# Sheet1.net
KiCad netlist of a schematic drawn in Altium Designer
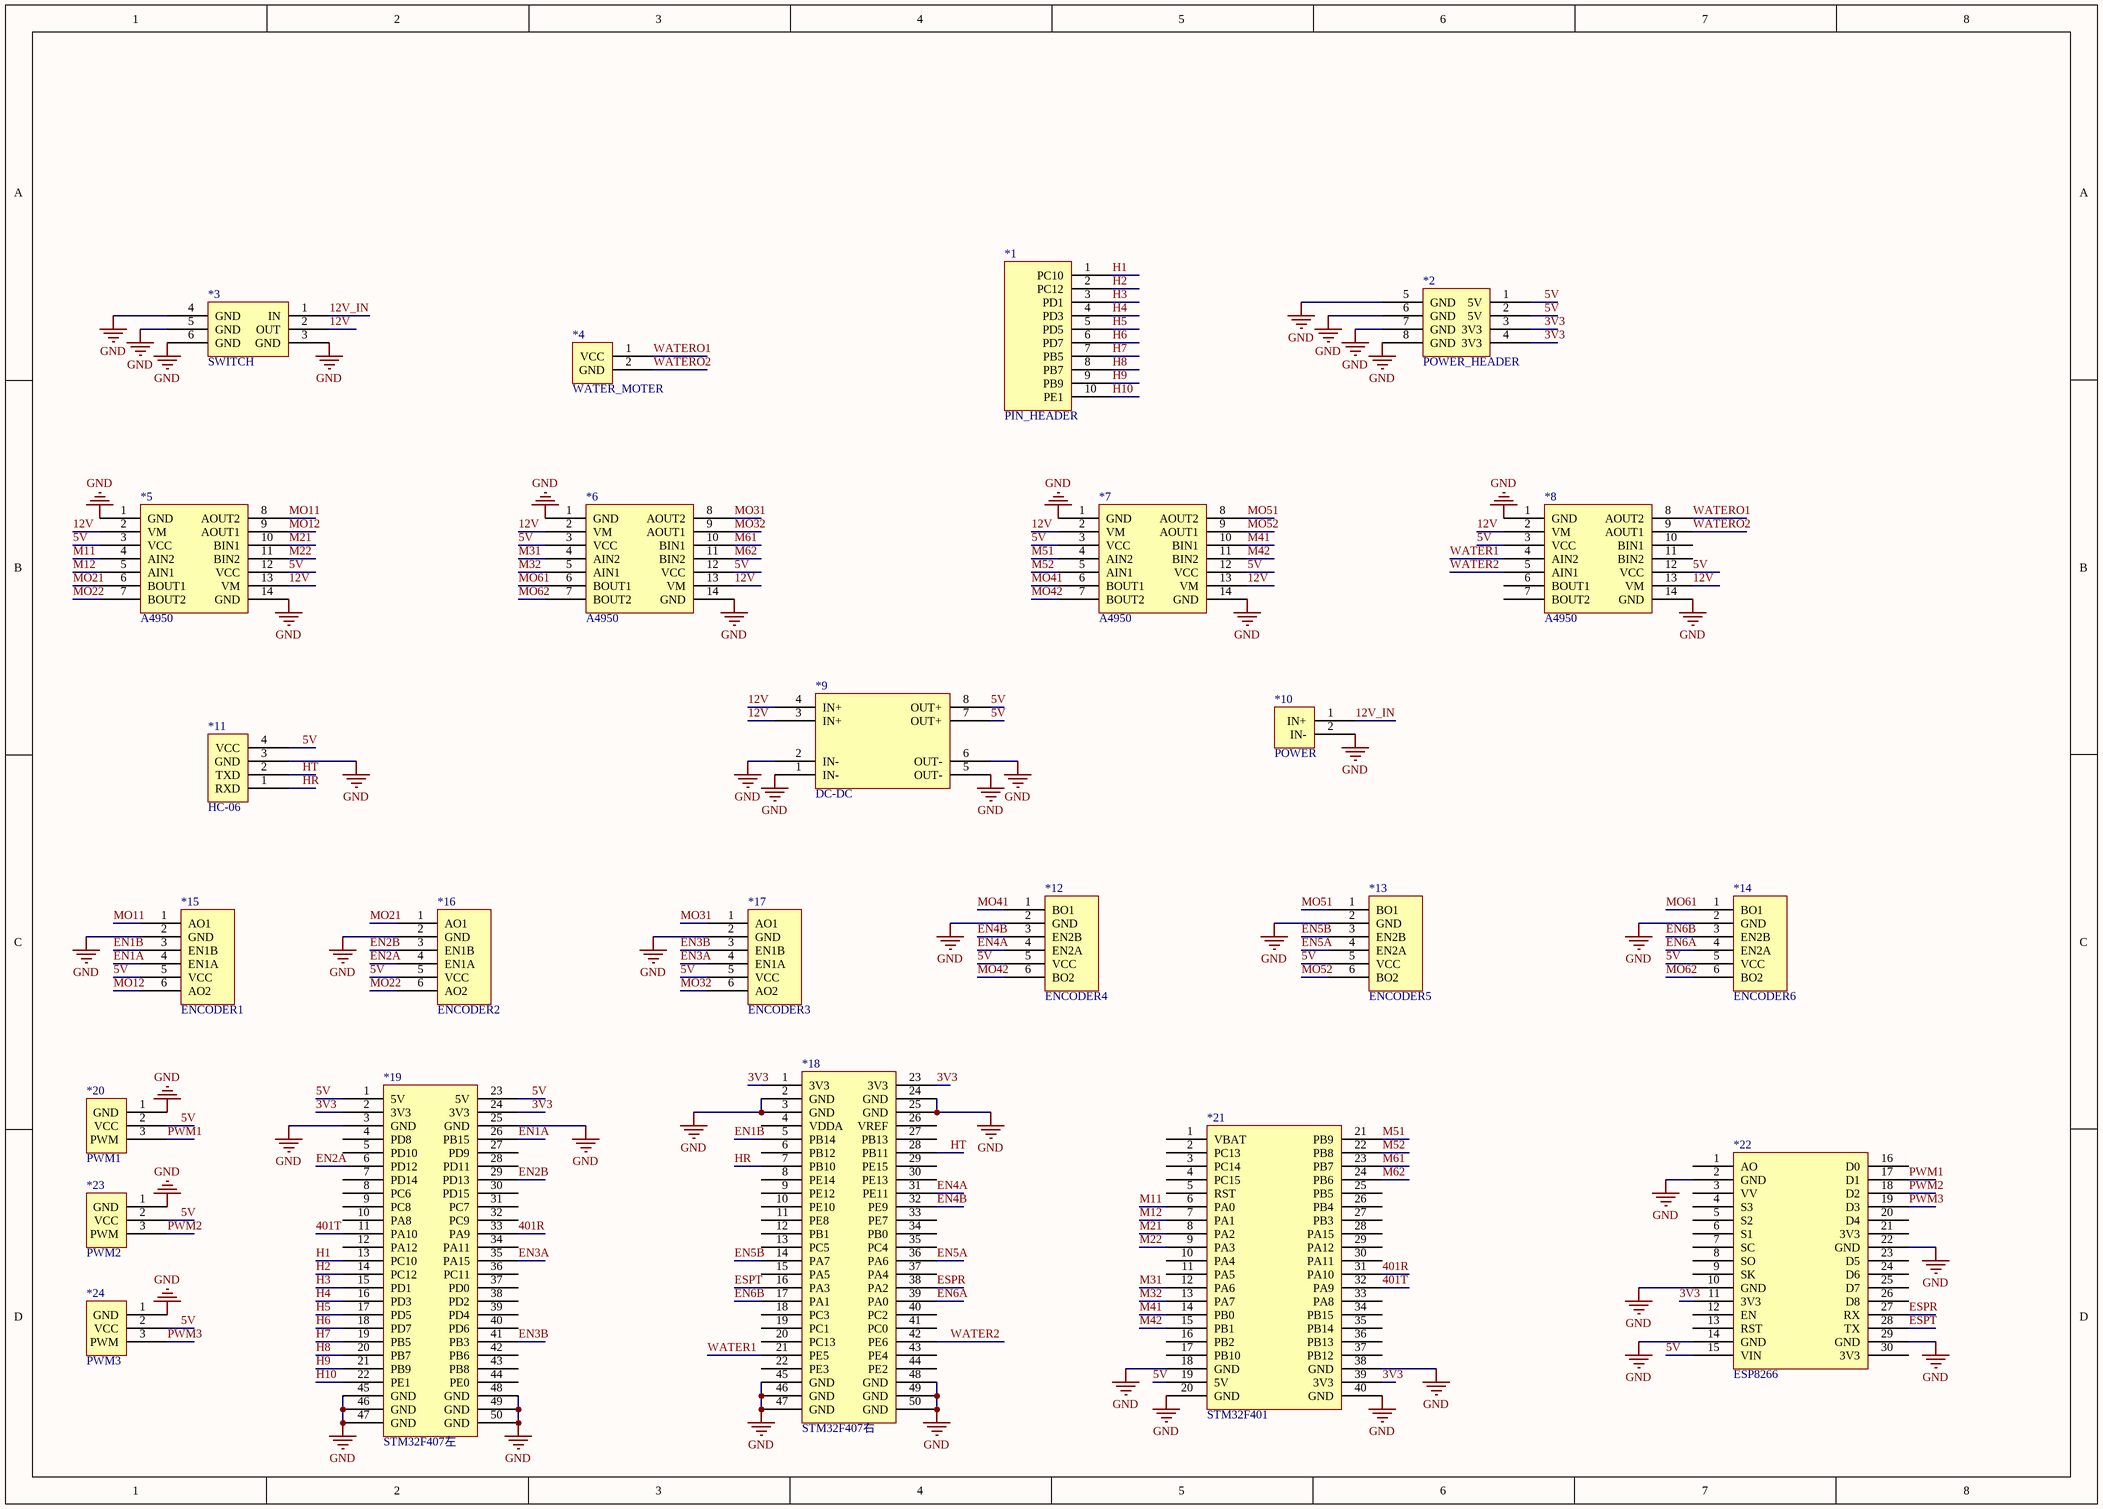
[diagram p0: Sheet1.SchDoc]

(export (version "E")
  (design (tool "Eeschema 10.0.6"))
  (components
    (comp (ref "*1")
      (value "PIN_HEADER")
      (footprint "PIN_HEADER")
      (libsource (lib "Schlib1") (part "PIN_HEADER"))
    )
    (comp (ref "*2")
      (value "POWER_HEADER")
      (footprint "POWER_HEADER")
      (libsource (lib "Schlib1") (part "POWER_HEADER"))
    )
    (comp (ref "*3") (value "SWITCH") (footprint "SIWITCH") (libsource (lib "Schlib1") (part "SWITCH")))
    (comp (ref "*4")
      (value "WATER_MOTER")
      (footprint "WATER_HEADER")
      (libsource (lib "Schlib1") (part "WATER_MOTER"))
    )
    (comp (ref "*5") (value "A4950") (footprint "A4950") (libsource (lib "Schlib1") (part "A4950")))
    (comp (ref "*6") (value "A4950") (footprint "A4950") (libsource (lib "Schlib1") (part "A4950")))
    (comp (ref "*7") (value "A4950") (footprint "A4950") (libsource (lib "Schlib1") (part "A4950")))
    (comp (ref "*8") (value "A4950") (footprint "A4950") (libsource (lib "Schlib1") (part "A4950")))
    (comp (ref "*9") (value "DC-DC") (footprint "DC-DC") (libsource (lib "Schlib1") (part "DC-DC")))
    (comp (ref "*10") (value "POWER") (footprint "POWER") (libsource (lib "Schlib1") (part "POWER")))
    (comp (ref "*11") (value "HC-06") (footprint "HC-06") (libsource (lib "Schlib1") (part "HC-06")))
    (comp (ref "*12") (value "ENCODER4") (footprint "ENCODER2") (libsource (lib "Schlib1") (part "ENCODER4")))
    (comp (ref "*13") (value "ENCODER5") (footprint "ENCODER2") (libsource (lib "Schlib1") (part "ENCODER5")))
    (comp (ref "*14") (value "ENCODER6") (footprint "ENCODER2") (libsource (lib "Schlib1") (part "ENCODER6")))
    (comp (ref "*15") (value "ENCODER1") (footprint "ENCODER1") (libsource (lib "Schlib1") (part "ENCODER1")))
    (comp (ref "*16") (value "ENCODER2") (footprint "ENCODER1") (libsource (lib "Schlib1") (part "ENCODER2")))
    (comp (ref "*17") (value "ENCODER3") (footprint "ENCODER1") (libsource (lib "Schlib1") (part "ENCODER3")))
    (comp (ref "*18")
      (value "STM32F407右")
      (footprint "STM32F407左")
      (libsource (lib "Schlib1") (part "STM32F407右"))
    )
    (comp (ref "*19")
      (value "STM32F407左")
      (footprint "STM32F407左")
      (libsource (lib "Schlib1") (part "STM32F407左"))
    )
    (comp (ref "*20") (value "PWM1") (footprint "PWM") (libsource (lib "Schlib1") (part "PWM1")))
    (comp (ref "*21")
      (value "STM32F401")
      (footprint "STM32F401CCU6")
      (libsource (lib "Schlib1") (part "STM32F401"))
    )
    (comp (ref "*22") (value "ESP8266") (footprint "ESP") (libsource (lib "Schlib1") (part "ESP8266")))
    (comp (ref "*23") (value "PWM2") (footprint "PWM") (libsource (lib "Schlib1") (part "PWM2")))
    (comp (ref "*24") (value "PWM3") (footprint "PWM") (libsource (lib "Schlib1") (part "PWM3")))
  )
  (nets
    (net (code "1") (name "/3V3") (class "Default")
      (node (ref "*18") (pin "1") (pinfunction "3V3_1") (pintype "passive"))
      (node (ref "*18") (pin "23") (pinfunction "3V3_23") (pintype "passive"))
      (node (ref "*19") (pin "2") (pinfunction "3V3_2") (pintype "passive"))
      (node (ref "*19") (pin "24") (pinfunction "3V3_24") (pintype "passive"))
      (node (ref "*2") (pin "3") (pinfunction "3V3_3") (pintype "passive"))
      (node (ref "*2") (pin "4") (pinfunction "3V3_4") (pintype "passive"))
      (node (ref "*21") (pin "39") (pinfunction "3V3_39") (pintype "passive"))
      (node (ref "*22") (pin "11") (pinfunction "3V3_11") (pintype "passive"))
    )
    (net (code "2") (name "/5V") (class "Default")
      (node (ref "*11") (pin "4") (pinfunction "VCC_4") (pintype "passive"))
      (node (ref "*12") (pin "5") (pinfunction "VCC_5") (pintype "passive"))
      (node (ref "*13") (pin "5") (pinfunction "VCC_5") (pintype "passive"))
      (node (ref "*14") (pin "5") (pinfunction "VCC_5") (pintype "passive"))
      (node (ref "*15") (pin "5") (pinfunction "VCC_5") (pintype "passive"))
      (node (ref "*16") (pin "5") (pinfunction "VCC_5") (pintype "passive"))
      (node (ref "*17") (pin "5") (pinfunction "VCC_5") (pintype "passive"))
      (node (ref "*19") (pin "1") (pinfunction "5V_1") (pintype "passive"))
      (node (ref "*19") (pin "23") (pinfunction "5V_23") (pintype "passive"))
      (node (ref "*2") (pin "1") (pinfunction "5V_1") (pintype "passive"))
      (node (ref "*2") (pin "2") (pinfunction "5V_2") (pintype "passive"))
      (node (ref "*20") (pin "2") (pinfunction "VCC_2") (pintype "passive"))
      (node (ref "*21") (pin "19") (pinfunction "5V_19") (pintype "passive"))
      (node (ref "*22") (pin "15") (pinfunction "VIN_15") (pintype "passive"))
      (node (ref "*23") (pin "2") (pinfunction "VCC_2") (pintype "passive"))
      (node (ref "*24") (pin "2") (pinfunction "VCC_2") (pintype "passive"))
      (node (ref "*5") (pin "12") (pinfunction "VCC_12") (pintype "passive"))
      (node (ref "*5") (pin "3") (pinfunction "VCC_3") (pintype "passive"))
      (node (ref "*6") (pin "12") (pinfunction "VCC_12") (pintype "passive"))
      (node (ref "*6") (pin "3") (pinfunction "VCC_3") (pintype "passive"))
      (node (ref "*7") (pin "12") (pinfunction "VCC_12") (pintype "passive"))
      (node (ref "*7") (pin "3") (pinfunction "VCC_3") (pintype "passive"))
      (node (ref "*8") (pin "12") (pinfunction "VCC_12") (pintype "passive"))
      (node (ref "*8") (pin "3") (pinfunction "VCC_3") (pintype "passive"))
      (node (ref "*9") (pin "7") (pinfunction "OUT+_7") (pintype "passive"))
      (node (ref "*9") (pin "8") (pinfunction "OUT+_8") (pintype "passive"))
    )
    (net (code "3") (name "/12V") (class "Default")
      (node (ref "*3") (pin "2") (pinfunction "OUT_2") (pintype "passive"))
      (node (ref "*5") (pin "13") (pinfunction "VM_13") (pintype "passive"))
      (node (ref "*5") (pin "2") (pinfunction "VM_2") (pintype "passive"))
      (node (ref "*6") (pin "13") (pinfunction "VM_13") (pintype "passive"))
      (node (ref "*6") (pin "2") (pinfunction "VM_2") (pintype "passive"))
      (node (ref "*7") (pin "13") (pinfunction "VM_13") (pintype "passive"))
      (node (ref "*7") (pin "2") (pinfunction "VM_2") (pintype "passive"))
      (node (ref "*8") (pin "13") (pinfunction "VM_13") (pintype "passive"))
      (node (ref "*8") (pin "2") (pinfunction "VM_2") (pintype "passive"))
      (node (ref "*9") (pin "3") (pinfunction "IN+_3") (pintype "passive"))
      (node (ref "*9") (pin "4") (pinfunction "IN+_4") (pintype "passive"))
    )
    (net (code "4") (name "/12V_IN") (class "Default")
      (node (ref "*10") (pin "1") (pinfunction "IN+_1") (pintype "passive"))
      (node (ref "*3") (pin "1") (pinfunction "IN_1") (pintype "passive"))
    )
    (net (code "5") (name "/401R") (class "Default")
      (node (ref "*19") (pin "33") (pinfunction "PA9_33") (pintype "passive"))
      (node (ref "*21") (pin "31") (pinfunction "PA10_31") (pintype "passive"))
    )
    (net (code "6") (name "/401T") (class "Default")
      (node (ref "*19") (pin "11") (pinfunction "PA10_11") (pintype "passive"))
      (node (ref "*21") (pin "32") (pinfunction "PA9_32") (pintype "passive"))
    )
    (net (code "7") (name "/EN1A") (class "Default")
      (node (ref "*15") (pin "4") (pinfunction "EN1A_4") (pintype "passive"))
      (node (ref "*19") (pin "26") (pinfunction "PB15_26") (pintype "passive"))
    )
    (net (code "8") (name "/EN1B") (class "Default")
      (node (ref "*15") (pin "3") (pinfunction "EN1B_3") (pintype "passive"))
      (node (ref "*18") (pin "5") (pinfunction "PB14_5") (pintype "passive"))
    )
    (net (code "9") (name "/EN2A") (class "Default")
      (node (ref "*16") (pin "4") (pinfunction "EN1A_4") (pintype "passive"))
      (node (ref "*19") (pin "6") (pinfunction "PD12_6") (pintype "passive"))
    )
    (net (code "10") (name "/EN2B") (class "Default")
      (node (ref "*16") (pin "3") (pinfunction "EN1B_3") (pintype "passive"))
      (node (ref "*19") (pin "29") (pinfunction "PD13_29") (pintype "passive"))
    )
    (net (code "11") (name "/EN3A") (class "Default")
      (node (ref "*17") (pin "4") (pinfunction "EN1A_4") (pintype "passive"))
      (node (ref "*19") (pin "35") (pinfunction "PA15_35") (pintype "passive"))
    )
    (net (code "12") (name "/EN3B") (class "Default")
      (node (ref "*17") (pin "3") (pinfunction "EN1B_3") (pintype "passive"))
      (node (ref "*19") (pin "41") (pinfunction "PB3_41") (pintype "passive"))
    )
    (net (code "13") (name "/EN4A") (class "Default")
      (node (ref "*12") (pin "4") (pinfunction "EN2A_4") (pintype "passive"))
      (node (ref "*18") (pin "31") (pinfunction "PE11_31") (pintype "passive"))
    )
    (net (code "14") (name "/EN4B") (class "Default")
      (node (ref "*12") (pin "3") (pinfunction "EN2B_3") (pintype "passive"))
      (node (ref "*18") (pin "32") (pinfunction "PE9_32") (pintype "passive"))
    )
    (net (code "15") (name "/EN5A") (class "Default")
      (node (ref "*13") (pin "4") (pinfunction "EN2A_4") (pintype "passive"))
      (node (ref "*18") (pin "36") (pinfunction "PA6_36") (pintype "passive"))
    )
    (net (code "16") (name "/EN5B") (class "Default")
      (node (ref "*13") (pin "3") (pinfunction "EN2B_3") (pintype "passive"))
      (node (ref "*18") (pin "14") (pinfunction "PA7_14") (pintype "passive"))
    )
    (net (code "17") (name "/EN6A") (class "Default")
      (node (ref "*14") (pin "4") (pinfunction "EN2A_4") (pintype "passive"))
      (node (ref "*18") (pin "39") (pinfunction "PA0_39") (pintype "passive"))
    )
    (net (code "18") (name "/EN6B") (class "Default")
      (node (ref "*14") (pin "3") (pinfunction "EN2B_3") (pintype "passive"))
      (node (ref "*18") (pin "17") (pinfunction "PA1_17") (pintype "passive"))
    )
    (net (code "19") (name "/ESPR") (class "Default")
      (node (ref "*18") (pin "38") (pinfunction "PA2_38") (pintype "passive"))
      (node (ref "*22") (pin "27") (pinfunction "RX_27") (pintype "passive"))
    )
    (net (code "20") (name "/ESPT") (class "Default")
      (node (ref "*18") (pin "16") (pinfunction "PA3_16") (pintype "passive"))
      (node (ref "*22") (pin "28") (pinfunction "TX_28") (pintype "passive"))
    )
    (net (code "21") (name "/H1") (class "Default")
      (node (ref "*1") (pin "1") (pinfunction "PC10_1") (pintype "passive"))
      (node (ref "*19") (pin "13") (pinfunction "PC10_13") (pintype "passive"))
    )
    (net (code "22") (name "/H2") (class "Default")
      (node (ref "*1") (pin "2") (pinfunction "PC12_2") (pintype "passive"))
      (node (ref "*19") (pin "14") (pinfunction "PC12_14") (pintype "passive"))
    )
    (net (code "23") (name "/H3") (class "Default")
      (node (ref "*1") (pin "3") (pinfunction "PD1_3") (pintype "passive"))
      (node (ref "*19") (pin "15") (pinfunction "PD1_15") (pintype "passive"))
    )
    (net (code "24") (name "/H4") (class "Default")
      (node (ref "*1") (pin "4") (pinfunction "PD3_4") (pintype "passive"))
      (node (ref "*19") (pin "16") (pinfunction "PD3_16") (pintype "passive"))
    )
    (net (code "25") (name "/H5") (class "Default")
      (node (ref "*1") (pin "5") (pinfunction "PD5_5") (pintype "passive"))
      (node (ref "*19") (pin "17") (pinfunction "PD5_17") (pintype "passive"))
    )
    (net (code "26") (name "/H6") (class "Default")
      (node (ref "*1") (pin "6") (pinfunction "PD7_6") (pintype "passive"))
      (node (ref "*19") (pin "18") (pinfunction "PD7_18") (pintype "passive"))
    )
    (net (code "27") (name "/H7") (class "Default")
      (node (ref "*1") (pin "7") (pinfunction "PB5_7") (pintype "passive"))
      (node (ref "*19") (pin "19") (pinfunction "PB5_19") (pintype "passive"))
    )
    (net (code "28") (name "/H8") (class "Default")
      (node (ref "*1") (pin "8") (pinfunction "PB7_8") (pintype "passive"))
      (node (ref "*19") (pin "20") (pinfunction "PB7_20") (pintype "passive"))
    )
    (net (code "29") (name "/H9") (class "Default")
      (node (ref "*1") (pin "9") (pinfunction "PB9_9") (pintype "passive"))
      (node (ref "*19") (pin "21") (pinfunction "PB9_21") (pintype "passive"))
    )
    (net (code "30") (name "/H10") (class "Default")
      (node (ref "*1") (pin "10") (pinfunction "PE1_10") (pintype "passive"))
      (node (ref "*19") (pin "22") (pinfunction "PE1_22") (pintype "passive"))
    )
    (net (code "31") (name "/HR") (class "Default")
      (node (ref "*11") (pin "1") (pinfunction "RXD_1") (pintype "passive"))
      (node (ref "*18") (pin "7") (pinfunction "PB10_7") (pintype "passive"))
    )
    (net (code "32") (name "/HT") (class "Default")
      (node (ref "*11") (pin "2") (pinfunction "TXD_2") (pintype "passive"))
      (node (ref "*18") (pin "28") (pinfunction "PB11_28") (pintype "passive"))
    )
    (net (code "33") (name "/M11") (class "Default")
      (node (ref "*21") (pin "6") (pinfunction "PA0_6") (pintype "passive"))
      (node (ref "*5") (pin "4") (pinfunction "AIN2_4") (pintype "passive"))
    )
    (net (code "34") (name "/M12") (class "Default")
      (node (ref "*21") (pin "7") (pinfunction "PA1_7") (pintype "passive"))
      (node (ref "*5") (pin "5") (pinfunction "AIN1_5") (pintype "passive"))
    )
    (net (code "35") (name "/M21") (class "Default")
      (node (ref "*21") (pin "8") (pinfunction "PA2_8") (pintype "passive"))
      (node (ref "*5") (pin "10") (pinfunction "BIN1_10") (pintype "passive"))
    )
    (net (code "36") (name "/M22") (class "Default")
      (node (ref "*21") (pin "9") (pinfunction "PA3_9") (pintype "passive"))
      (node (ref "*5") (pin "11") (pinfunction "BIN2_11") (pintype "passive"))
    )
    (net (code "37") (name "/M31") (class "Default")
      (node (ref "*21") (pin "12") (pinfunction "PA6_12") (pintype "passive"))
      (node (ref "*6") (pin "4") (pinfunction "AIN2_4") (pintype "passive"))
    )
    (net (code "38") (name "/M32") (class "Default")
      (node (ref "*21") (pin "13") (pinfunction "PA7_13") (pintype "passive"))
      (node (ref "*6") (pin "5") (pinfunction "AIN1_5") (pintype "passive"))
    )
    (net (code "39") (name "/M41") (class "Default")
      (node (ref "*21") (pin "14") (pinfunction "PB0_14") (pintype "passive"))
      (node (ref "*7") (pin "10") (pinfunction "BIN1_10") (pintype "passive"))
    )
    (net (code "40") (name "/M42") (class "Default")
      (node (ref "*21") (pin "15") (pinfunction "PB1_15") (pintype "passive"))
      (node (ref "*7") (pin "11") (pinfunction "BIN2_11") (pintype "passive"))
    )
    (net (code "41") (name "/M51") (class "Default")
      (node (ref "*21") (pin "21") (pinfunction "PB9_21") (pintype "passive"))
      (node (ref "*7") (pin "4") (pinfunction "AIN2_4") (pintype "passive"))
    )
    (net (code "42") (name "/M52") (class "Default")
      (node (ref "*21") (pin "22") (pinfunction "PB8_22") (pintype "passive"))
      (node (ref "*7") (pin "5") (pinfunction "AIN1_5") (pintype "passive"))
    )
    (net (code "43") (name "/M61") (class "Default")
      (node (ref "*21") (pin "23") (pinfunction "PB7_23") (pintype "passive"))
      (node (ref "*6") (pin "10") (pinfunction "BIN1_10") (pintype "passive"))
    )
    (net (code "44") (name "/M62") (class "Default")
      (node (ref "*21") (pin "24") (pinfunction "PB6_24") (pintype "passive"))
      (node (ref "*6") (pin "11") (pinfunction "BIN2_11") (pintype "passive"))
    )
    (net (code "45") (name "/MO11") (class "Default")
      (node (ref "*15") (pin "1") (pinfunction "AO1_1") (pintype "passive"))
      (node (ref "*5") (pin "8") (pinfunction "AOUT2_8") (pintype "passive"))
    )
    (net (code "46") (name "/MO12") (class "Default")
      (node (ref "*15") (pin "6") (pinfunction "AO2_6") (pintype "passive"))
      (node (ref "*5") (pin "9") (pinfunction "AOUT1_9") (pintype "passive"))
    )
    (net (code "47") (name "/MO21") (class "Default")
      (node (ref "*16") (pin "1") (pinfunction "AO1_1") (pintype "passive"))
      (node (ref "*5") (pin "6") (pinfunction "BOUT1_6") (pintype "passive"))
    )
    (net (code "48") (name "/MO22") (class "Default")
      (node (ref "*16") (pin "6") (pinfunction "AO2_6") (pintype "passive"))
      (node (ref "*5") (pin "7") (pinfunction "BOUT2_7") (pintype "passive"))
    )
    (net (code "49") (name "/MO31") (class "Default")
      (node (ref "*17") (pin "1") (pinfunction "AO1_1") (pintype "passive"))
      (node (ref "*6") (pin "8") (pinfunction "AOUT2_8") (pintype "passive"))
    )
    (net (code "50") (name "/MO32") (class "Default")
      (node (ref "*17") (pin "6") (pinfunction "AO2_6") (pintype "passive"))
      (node (ref "*6") (pin "9") (pinfunction "AOUT1_9") (pintype "passive"))
    )
    (net (code "51") (name "/MO41") (class "Default")
      (node (ref "*12") (pin "1") (pinfunction "BO1_1") (pintype "passive"))
      (node (ref "*7") (pin "6") (pinfunction "BOUT1_6") (pintype "passive"))
    )
    (net (code "52") (name "/MO42") (class "Default")
      (node (ref "*12") (pin "6") (pinfunction "BO2_6") (pintype "passive"))
      (node (ref "*7") (pin "7") (pinfunction "BOUT2_7") (pintype "passive"))
    )
    (net (code "53") (name "/MO51") (class "Default")
      (node (ref "*13") (pin "1") (pinfunction "BO1_1") (pintype "passive"))
      (node (ref "*7") (pin "8") (pinfunction "AOUT2_8") (pintype "passive"))
    )
    (net (code "54") (name "/MO52") (class "Default")
      (node (ref "*13") (pin "6") (pinfunction "BO2_6") (pintype "passive"))
      (node (ref "*7") (pin "9") (pinfunction "AOUT1_9") (pintype "passive"))
    )
    (net (code "55") (name "/MO61") (class "Default")
      (node (ref "*14") (pin "1") (pinfunction "BO1_1") (pintype "passive"))
      (node (ref "*6") (pin "6") (pinfunction "BOUT1_6") (pintype "passive"))
    )
    (net (code "56") (name "/MO62") (class "Default")
      (node (ref "*14") (pin "6") (pinfunction "BO2_6") (pintype "passive"))
      (node (ref "*6") (pin "7") (pinfunction "BOUT2_7") (pintype "passive"))
    )
    (net (code "57") (name "/PWM1") (class "Default")
      (node (ref "*20") (pin "3") (pinfunction "PWM_3") (pintype "passive"))
      (node (ref "*22") (pin "17") (pinfunction "D1_17") (pintype "passive"))
    )
    (net (code "58") (name "/PWM2") (class "Default")
      (node (ref "*22") (pin "18") (pinfunction "D2_18") (pintype "passive"))
      (node (ref "*23") (pin "3") (pinfunction "PWM_3") (pintype "passive"))
    )
    (net (code "59") (name "/PWM3") (class "Default")
      (node (ref "*22") (pin "19") (pinfunction "D3_19") (pintype "passive"))
      (node (ref "*24") (pin "3") (pinfunction "PWM_3") (pintype "passive"))
    )
    (net (code "60") (name "/WATER1") (class "Default")
      (node (ref "*18") (pin "21") (pinfunction "PE5_21") (pintype "passive"))
      (node (ref "*8") (pin "4") (pinfunction "AIN2_4") (pintype "passive"))
    )
    (net (code "61") (name "/WATER2") (class "Default")
      (node (ref "*18") (pin "42") (pinfunction "PE6_42") (pintype "passive"))
      (node (ref "*8") (pin "5") (pinfunction "AIN1_5") (pintype "passive"))
    )
    (net (code "62") (name "/WATERO1") (class "Default")
      (node (ref "*4") (pin "1") (pinfunction "VCC_1") (pintype "passive"))
      (node (ref "*8") (pin "8") (pinfunction "AOUT2_8") (pintype "passive"))
    )
    (net (code "63") (name "/WATERO2") (class "Default")
      (node (ref "*4") (pin "2") (pinfunction "GND_2") (pintype "passive"))
      (node (ref "*8") (pin "9") (pinfunction "AOUT1_9") (pintype "passive"))
    )
    (net (code "64") (name "GND") (class "Default")
      (node (ref "*10") (pin "2") (pinfunction "IN-_2") (pintype "passive"))
      (node (ref "*11") (pin "3") (pinfunction "GND_3") (pintype "passive"))
      (node (ref "*12") (pin "2") (pinfunction "GND_2") (pintype "passive"))
      (node (ref "*13") (pin "2") (pinfunction "GND_2") (pintype "passive"))
      (node (ref "*14") (pin "2") (pinfunction "GND_2") (pintype "passive"))
      (node (ref "*15") (pin "2") (pinfunction "GND_2") (pintype "passive"))
      (node (ref "*16") (pin "2") (pinfunction "GND_2") (pintype "passive"))
      (node (ref "*17") (pin "2") (pinfunction "GND_2") (pintype "passive"))
      (node (ref "*18") (pin "2") (pinfunction "GND_2") (pintype "passive"))
      (node (ref "*18") (pin "24") (pinfunction "GND_24") (pintype "passive"))
      (node (ref "*18") (pin "25") (pinfunction "GND_25") (pintype "passive"))
      (node (ref "*18") (pin "3") (pinfunction "GND_3") (pintype "passive"))
      (node (ref "*18") (pin "45") (pinfunction "GND_45") (pintype "passive"))
      (node (ref "*18") (pin "46") (pinfunction "GND_46") (pintype "passive"))
      (node (ref "*18") (pin "47") (pinfunction "GND_47") (pintype "passive"))
      (node (ref "*18") (pin "48") (pinfunction "GND_48") (pintype "passive"))
      (node (ref "*18") (pin "49") (pinfunction "GND_49") (pintype "passive"))
      (node (ref "*18") (pin "50") (pinfunction "GND_50") (pintype "passive"))
      (node (ref "*19") (pin "25") (pinfunction "GND_25") (pintype "passive"))
      (node (ref "*19") (pin "3") (pinfunction "GND_3") (pintype "passive"))
      (node (ref "*19") (pin "45") (pinfunction "GND_45") (pintype "passive"))
      (node (ref "*19") (pin "46") (pinfunction "GND_46") (pintype "passive"))
      (node (ref "*19") (pin "47") (pinfunction "GND_47") (pintype "passive"))
      (node (ref "*19") (pin "48") (pinfunction "GND_48") (pintype "passive"))
      (node (ref "*19") (pin "49") (pinfunction "GND_49") (pintype "passive"))
      (node (ref "*19") (pin "50") (pinfunction "GND_50") (pintype "passive"))
      (node (ref "*2") (pin "5") (pinfunction "GND_5") (pintype "passive"))
      (node (ref "*2") (pin "6") (pinfunction "GND_6") (pintype "passive"))
      (node (ref "*2") (pin "7") (pinfunction "GND_7") (pintype "passive"))
      (node (ref "*2") (pin "8") (pinfunction "GND_8") (pintype "passive"))
      (node (ref "*20") (pin "1") (pinfunction "GND_1") (pintype "passive"))
      (node (ref "*21") (pin "18") (pinfunction "GND_18") (pintype "passive"))
      (node (ref "*21") (pin "20") (pinfunction "GND_20") (pintype "passive"))
      (node (ref "*21") (pin "38") (pinfunction "GND_38") (pintype "passive"))
      (node (ref "*21") (pin "40") (pinfunction "GND_40") (pintype "passive"))
      (node (ref "*22") (pin "10") (pinfunction "GND_10") (pintype "passive"))
      (node (ref "*22") (pin "14") (pinfunction "GND_14") (pintype "passive"))
      (node (ref "*22") (pin "2") (pinfunction "GND_2") (pintype "passive"))
      (node (ref "*22") (pin "22") (pinfunction "GND_22") (pintype "passive"))
      (node (ref "*22") (pin "29") (pinfunction "GND_29") (pintype "passive"))
      (node (ref "*23") (pin "1") (pinfunction "GND_1") (pintype "passive"))
      (node (ref "*24") (pin "1") (pinfunction "GND_1") (pintype "passive"))
      (node (ref "*3") (pin "3") (pinfunction "GND_3") (pintype "passive"))
      (node (ref "*3") (pin "4") (pinfunction "GND_4") (pintype "passive"))
      (node (ref "*3") (pin "5") (pinfunction "GND_5") (pintype "passive"))
      (node (ref "*3") (pin "6") (pinfunction "GND_6") (pintype "passive"))
      (node (ref "*5") (pin "1") (pinfunction "GND_1") (pintype "passive"))
      (node (ref "*5") (pin "14") (pinfunction "GND_14") (pintype "passive"))
      (node (ref "*6") (pin "1") (pinfunction "GND_1") (pintype "passive"))
      (node (ref "*6") (pin "14") (pinfunction "GND_14") (pintype "passive"))
      (node (ref "*7") (pin "1") (pinfunction "GND_1") (pintype "passive"))
      (node (ref "*7") (pin "14") (pinfunction "GND_14") (pintype "passive"))
      (node (ref "*8") (pin "1") (pinfunction "GND_1") (pintype "passive"))
      (node (ref "*8") (pin "14") (pinfunction "GND_14") (pintype "passive"))
      (node (ref "*9") (pin "1") (pinfunction "IN-_1") (pintype "passive"))
      (node (ref "*9") (pin "2") (pinfunction "IN-_2") (pintype "passive"))
      (node (ref "*9") (pin "5") (pinfunction "OUT-_5") (pintype "passive"))
      (node (ref "*9") (pin "6") (pinfunction "OUT-_6") (pintype "passive"))
    )
    (net (code "65") (name "unconnected-(*8-BIN1-Pad10)") (class "Default")
      (node (ref "*8") (pin "10") (pinfunction "BIN1_10") (pintype "passive"))
    )
    (net (code "66") (name "unconnected-(*8-BIN2-Pad11)") (class "Default")
      (node (ref "*8") (pin "11") (pinfunction "BIN2_11") (pintype "passive"))
    )
    (net (code "67") (name "unconnected-(*8-BOUT1-Pad6)") (class "Default")
      (node (ref "*8") (pin "6") (pinfunction "BOUT1_6") (pintype "passive"))
    )
    (net (code "68") (name "unconnected-(*8-BOUT2-Pad7)") (class "Default")
      (node (ref "*8") (pin "7") (pinfunction "BOUT2_7") (pintype "passive"))
    )
    (net (code "69") (name "unconnected-(*18-PA4-Pad37)") (class "Default")
      (node (ref "*18") (pin "37") (pinfunction "PA4_37") (pintype "passive"))
    )
    (net (code "70") (name "unconnected-(*18-PA5-Pad15)") (class "Default")
      (node (ref "*18") (pin "15") (pinfunction "PA5_15") (pintype "passive"))
    )
    (net (code "71") (name "unconnected-(*18-PB0-Pad34)") (class "Default")
      (node (ref "*18") (pin "34") (pinfunction "PB0_34") (pintype "passive"))
    )
    (net (code "72") (name "unconnected-(*18-PB1-Pad12)") (class "Default")
      (node (ref "*18") (pin "12") (pinfunction "PB1_12") (pintype "passive"))
    )
    (net (code "73") (name "unconnected-(*18-PB12-Pad6)") (class "Default")
      (node (ref "*18") (pin "6") (pinfunction "PB12_6") (pintype "passive"))
    )
    (net (code "74") (name "unconnected-(*18-PB13-Pad27)") (class "Default")
      (node (ref "*18") (pin "27") (pinfunction "PB13_27") (pintype "passive"))
    )
    (net (code "75") (name "unconnected-(*18-PC0-Pad41)") (class "Default")
      (node (ref "*18") (pin "41") (pinfunction "PC0_41") (pintype "passive"))
    )
    (net (code "76") (name "unconnected-(*18-PC1-Pad19)") (class "Default")
      (node (ref "*18") (pin "19") (pinfunction "PC1_19") (pintype "passive"))
    )
    (net (code "77") (name "unconnected-(*18-PC2-Pad40)") (class "Default")
      (node (ref "*18") (pin "40") (pinfunction "PC2_40") (pintype "passive"))
    )
    (net (code "78") (name "unconnected-(*18-PC3-Pad18)") (class "Default")
      (node (ref "*18") (pin "18") (pinfunction "PC3_18") (pintype "passive"))
    )
    (net (code "79") (name "unconnected-(*18-PC4-Pad35)") (class "Default")
      (node (ref "*18") (pin "35") (pinfunction "PC4_35") (pintype "passive"))
    )
    (net (code "80") (name "unconnected-(*18-PC5-Pad13)") (class "Default")
      (node (ref "*18") (pin "13") (pinfunction "PC5_13") (pintype "passive"))
    )
    (net (code "81") (name "unconnected-(*18-PC13-Pad20)") (class "Default")
      (node (ref "*18") (pin "20") (pinfunction "PC13_20") (pintype "passive"))
    )
    (net (code "82") (name "unconnected-(*18-PE2-Pad44)") (class "Default")
      (node (ref "*18") (pin "44") (pinfunction "PE2_44") (pintype "passive"))
    )
    (net (code "83") (name "unconnected-(*18-PE3-Pad22)") (class "Default")
      (node (ref "*18") (pin "22") (pinfunction "PE3_22") (pintype "passive"))
    )
    (net (code "84") (name "unconnected-(*18-PE4-Pad43)") (class "Default")
      (node (ref "*18") (pin "43") (pinfunction "PE4_43") (pintype "passive"))
    )
    (net (code "85") (name "unconnected-(*18-PE7-Pad33)") (class "Default")
      (node (ref "*18") (pin "33") (pinfunction "PE7_33") (pintype "passive"))
    )
    (net (code "86") (name "unconnected-(*18-PE8-Pad11)") (class "Default")
      (node (ref "*18") (pin "11") (pinfunction "PE8_11") (pintype "passive"))
    )
    (net (code "87") (name "unconnected-(*18-PE10-Pad10)") (class "Default")
      (node (ref "*18") (pin "10") (pinfunction "PE10_10") (pintype "passive"))
    )
    (net (code "88") (name "unconnected-(*18-PE12-Pad9)") (class "Default")
      (node (ref "*18") (pin "9") (pinfunction "PE12_9") (pintype "passive"))
    )
    (net (code "89") (name "unconnected-(*18-PE13-Pad30)") (class "Default")
      (node (ref "*18") (pin "30") (pinfunction "PE13_30") (pintype "passive"))
    )
    (net (code "90") (name "unconnected-(*18-PE14-Pad8)") (class "Default")
      (node (ref "*18") (pin "8") (pinfunction "PE14_8") (pintype "passive"))
    )
    (net (code "91") (name "unconnected-(*18-PE15-Pad29)") (class "Default")
      (node (ref "*18") (pin "29") (pinfunction "PE15_29") (pintype "passive"))
    )
    (net (code "92") (name "unconnected-(*18-VDDA-Pad4)") (class "Default")
      (node (ref "*18") (pin "4") (pinfunction "VDDA_4") (pintype "passive"))
    )
    (net (code "93") (name "unconnected-(*18-VREF-Pad26)") (class "Default")
      (node (ref "*18") (pin "26") (pinfunction "VREF_26") (pintype "passive"))
    )
    (net (code "94") (name "unconnected-(*19-PA8-Pad10)") (class "Default")
      (node (ref "*19") (pin "10") (pinfunction "PA8_10") (pintype "passive"))
    )
    (net (code "95") (name "unconnected-(*19-PA11-Pad34)") (class "Default")
      (node (ref "*19") (pin "34") (pinfunction "PA11_34") (pintype "passive"))
    )
    (net (code "96") (name "unconnected-(*19-PA12-Pad12)") (class "Default")
      (node (ref "*19") (pin "12") (pinfunction "PA12_12") (pintype "passive"))
    )
    (net (code "97") (name "unconnected-(*19-PB6-Pad42)") (class "Default")
      (node (ref "*19") (pin "42") (pinfunction "PB6_42") (pintype "passive"))
    )
    (net (code "98") (name "unconnected-(*19-PB8-Pad43)") (class "Default")
      (node (ref "*19") (pin "43") (pinfunction "PB8_43") (pintype "passive"))
    )
    (net (code "99") (name "unconnected-(*19-PC6-Pad8)") (class "Default")
      (node (ref "*19") (pin "8") (pinfunction "PC6_8") (pintype "passive"))
    )
    (net (code "100") (name "unconnected-(*19-PC7-Pad31)") (class "Default")
      (node (ref "*19") (pin "31") (pinfunction "PC7_31") (pintype "passive"))
    )
    (net (code "101") (name "unconnected-(*19-PC8-Pad9)") (class "Default")
      (node (ref "*19") (pin "9") (pinfunction "PC8_9") (pintype "passive"))
    )
    (net (code "102") (name "unconnected-(*19-PC9-Pad32)") (class "Default")
      (node (ref "*19") (pin "32") (pinfunction "PC9_32") (pintype "passive"))
    )
    (net (code "103") (name "unconnected-(*19-PC11-Pad36)") (class "Default")
      (node (ref "*19") (pin "36") (pinfunction "PC11_36") (pintype "passive"))
    )
    (net (code "104") (name "unconnected-(*19-PD0-Pad37)") (class "Default")
      (node (ref "*19") (pin "37") (pinfunction "PD0_37") (pintype "passive"))
    )
    (net (code "105") (name "unconnected-(*19-PD2-Pad38)") (class "Default")
      (node (ref "*19") (pin "38") (pinfunction "PD2_38") (pintype "passive"))
    )
    (net (code "106") (name "unconnected-(*19-PD4-Pad39)") (class "Default")
      (node (ref "*19") (pin "39") (pinfunction "PD4_39") (pintype "passive"))
    )
    (net (code "107") (name "unconnected-(*19-PD6-Pad40)") (class "Default")
      (node (ref "*19") (pin "40") (pinfunction "PD6_40") (pintype "passive"))
    )
    (net (code "108") (name "unconnected-(*19-PD8-Pad4)") (class "Default")
      (node (ref "*19") (pin "4") (pinfunction "PD8_4") (pintype "passive"))
    )
    (net (code "109") (name "unconnected-(*19-PD9-Pad27)") (class "Default")
      (node (ref "*19") (pin "27") (pinfunction "PD9_27") (pintype "passive"))
    )
    (net (code "110") (name "unconnected-(*19-PD10-Pad5)") (class "Default")
      (node (ref "*19") (pin "5") (pinfunction "PD10_5") (pintype "passive"))
    )
    (net (code "111") (name "unconnected-(*19-PD11-Pad28)") (class "Default")
      (node (ref "*19") (pin "28") (pinfunction "PD11_28") (pintype "passive"))
    )
    (net (code "112") (name "unconnected-(*19-PD14-Pad7)") (class "Default")
      (node (ref "*19") (pin "7") (pinfunction "PD14_7") (pintype "passive"))
    )
    (net (code "113") (name "unconnected-(*19-PD15-Pad30)") (class "Default")
      (node (ref "*19") (pin "30") (pinfunction "PD15_30") (pintype "passive"))
    )
    (net (code "114") (name "unconnected-(*19-PE0-Pad44)") (class "Default")
      (node (ref "*19") (pin "44") (pinfunction "PE0_44") (pintype "passive"))
    )
    (net (code "115") (name "unconnected-(*21-PA4-Pad10)") (class "Default")
      (node (ref "*21") (pin "10") (pinfunction "PA4_10") (pintype "passive"))
    )
    (net (code "116") (name "unconnected-(*21-PA5-Pad11)") (class "Default")
      (node (ref "*21") (pin "11") (pinfunction "PA5_11") (pintype "passive"))
    )
    (net (code "117") (name "unconnected-(*21-PA8-Pad33)") (class "Default")
      (node (ref "*21") (pin "33") (pinfunction "PA8_33") (pintype "passive"))
    )
    (net (code "118") (name "unconnected-(*21-PA11-Pad30)") (class "Default")
      (node (ref "*21") (pin "30") (pinfunction "PA11_30") (pintype "passive"))
    )
    (net (code "119") (name "unconnected-(*21-PA12-Pad29)") (class "Default")
      (node (ref "*21") (pin "29") (pinfunction "PA12_29") (pintype "passive"))
    )
    (net (code "120") (name "unconnected-(*21-PA15-Pad28)") (class "Default")
      (node (ref "*21") (pin "28") (pinfunction "PA15_28") (pintype "passive"))
    )
    (net (code "121") (name "unconnected-(*21-PB2-Pad16)") (class "Default")
      (node (ref "*21") (pin "16") (pinfunction "PB2_16") (pintype "passive"))
    )
    (net (code "122") (name "unconnected-(*21-PB3-Pad27)") (class "Default")
      (node (ref "*21") (pin "27") (pinfunction "PB3_27") (pintype "passive"))
    )
    (net (code "123") (name "unconnected-(*21-PB4-Pad26)") (class "Default")
      (node (ref "*21") (pin "26") (pinfunction "PB4_26") (pintype "passive"))
    )
    (net (code "124") (name "unconnected-(*21-PB5-Pad25)") (class "Default")
      (node (ref "*21") (pin "25") (pinfunction "PB5_25") (pintype "passive"))
    )
    (net (code "125") (name "unconnected-(*21-PB10-Pad17)") (class "Default")
      (node (ref "*21") (pin "17") (pinfunction "PB10_17") (pintype "passive"))
    )
    (net (code "126") (name "unconnected-(*21-PB12-Pad37)") (class "Default")
      (node (ref "*21") (pin "37") (pinfunction "PB12_37") (pintype "passive"))
    )
    (net (code "127") (name "unconnected-(*21-PB13-Pad36)") (class "Default")
      (node (ref "*21") (pin "36") (pinfunction "PB13_36") (pintype "passive"))
    )
    (net (code "128") (name "unconnected-(*21-PB14-Pad35)") (class "Default")
      (node (ref "*21") (pin "35") (pinfunction "PB14_35") (pintype "passive"))
    )
    (net (code "129") (name "unconnected-(*21-PB15-Pad34)") (class "Default")
      (node (ref "*21") (pin "34") (pinfunction "PB15_34") (pintype "passive"))
    )
    (net (code "130") (name "unconnected-(*21-PC13-Pad2)") (class "Default")
      (node (ref "*21") (pin "2") (pinfunction "PC13_2") (pintype "passive"))
    )
    (net (code "131") (name "unconnected-(*21-PC14-Pad3)") (class "Default")
      (node (ref "*21") (pin "3") (pinfunction "PC14_3") (pintype "passive"))
    )
    (net (code "132") (name "unconnected-(*21-PC15-Pad4)") (class "Default")
      (node (ref "*21") (pin "4") (pinfunction "PC15_4") (pintype "passive"))
    )
    (net (code "133") (name "unconnected-(*21-RST-Pad5)") (class "Default")
      (node (ref "*21") (pin "5") (pinfunction "RST_5") (pintype "passive"))
    )
    (net (code "134") (name "unconnected-(*21-VBAT-Pad1)") (class "Default")
      (node (ref "*21") (pin "1") (pinfunction "VBAT_1") (pintype "passive"))
    )
    (net (code "135") (name "unconnected-(*22-3V3-Pad21)") (class "Default")
      (node (ref "*22") (pin "21") (pinfunction "3V3_21") (pintype "passive"))
    )
    (net (code "136") (name "unconnected-(*22-3V3-Pad30)") (class "Default")
      (node (ref "*22") (pin "30") (pinfunction "3V3_30") (pintype "passive"))
    )
    (net (code "137") (name "unconnected-(*22-AO-Pad1)") (class "Default")
      (node (ref "*22") (pin "1") (pinfunction "AO_1") (pintype "passive"))
    )
    (net (code "138") (name "unconnected-(*22-D0-Pad16)") (class "Default")
      (node (ref "*22") (pin "16") (pinfunction "D0_16") (pintype "passive"))
    )
    (net (code "139") (name "unconnected-(*22-D4-Pad20)") (class "Default")
      (node (ref "*22") (pin "20") (pinfunction "D4_20") (pintype "passive"))
    )
    (net (code "140") (name "unconnected-(*22-D5-Pad23)") (class "Default")
      (node (ref "*22") (pin "23") (pinfunction "D5_23") (pintype "passive"))
    )
    (net (code "141") (name "unconnected-(*22-D6-Pad24)") (class "Default")
      (node (ref "*22") (pin "24") (pinfunction "D6_24") (pintype "passive"))
    )
    (net (code "142") (name "unconnected-(*22-D7-Pad25)") (class "Default")
      (node (ref "*22") (pin "25") (pinfunction "D7_25") (pintype "passive"))
    )
    (net (code "143") (name "unconnected-(*22-D8-Pad26)") (class "Default")
      (node (ref "*22") (pin "26") (pinfunction "D8_26") (pintype "passive"))
    )
    (net (code "144") (name "unconnected-(*22-EN-Pad12)") (class "Default")
      (node (ref "*22") (pin "12") (pinfunction "EN_12") (pintype "passive"))
    )
    (net (code "145") (name "unconnected-(*22-RST-Pad13)") (class "Default")
      (node (ref "*22") (pin "13") (pinfunction "RST_13") (pintype "passive"))
    )
    (net (code "146") (name "unconnected-(*22-S1-Pad6)") (class "Default")
      (node (ref "*22") (pin "6") (pinfunction "S1_6") (pintype "passive"))
    )
    (net (code "147") (name "unconnected-(*22-S2-Pad5)") (class "Default")
      (node (ref "*22") (pin "5") (pinfunction "S2_5") (pintype "passive"))
    )
    (net (code "148") (name "unconnected-(*22-S3-Pad4)") (class "Default")
      (node (ref "*22") (pin "4") (pinfunction "S3_4") (pintype "passive"))
    )
    (net (code "149") (name "unconnected-(*22-SC-Pad7)") (class "Default")
      (node (ref "*22") (pin "7") (pinfunction "SC_7") (pintype "passive"))
    )
    (net (code "150") (name "unconnected-(*22-SK-Pad9)") (class "Default")
      (node (ref "*22") (pin "9") (pinfunction "SK_9") (pintype "passive"))
    )
    (net (code "151") (name "unconnected-(*22-SO-Pad8)") (class "Default")
      (node (ref "*22") (pin "8") (pinfunction "SO_8") (pintype "passive"))
    )
    (net (code "152") (name "unconnected-(*22-VV-Pad3)") (class "Default")
      (node (ref "*22") (pin "3") (pinfunction "VV_3") (pintype "passive"))
    )
  )
)
